# TweetyBoy.net
KiCad netlist of a schematic drawn in EAGLE
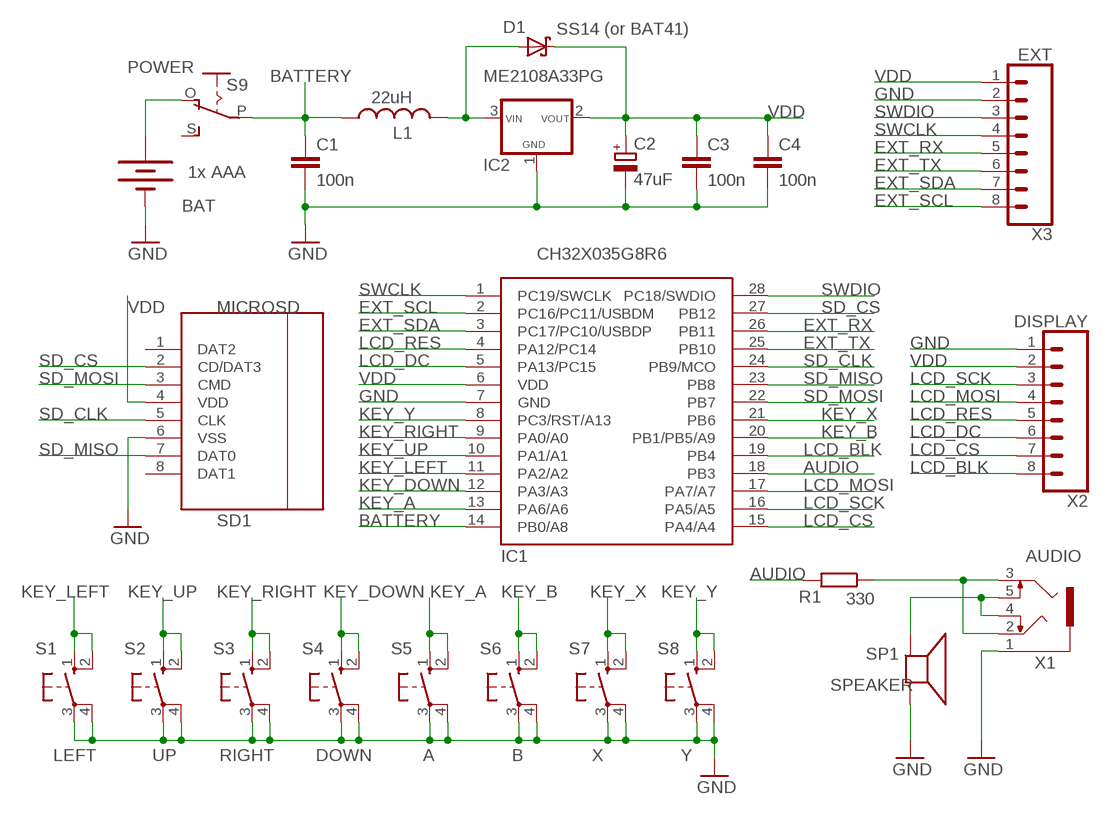
[diagram p0: schematic, sheet 1]

(export (version "E")
  (design (tool "Eeschema 10.0.6"))
  (components
    (comp (ref "BAT")
      (value "1x AAA")
      (footprint "eagle-import:BATTERY-AAA-KIT")
      (libsource (lib "eagle-import") (part "BATTERY-AAA_KIT"))
    )
    (comp (ref "C1")
      (value "100n")
      (footprint "eagle-import:C050-024X044")
      (libsource (lib "eagle-import") (part "C-EU050-024X044"))
    )
    (comp (ref "C2")
      (value "47uF")
      (footprint "eagle-import:E2-5")
      (libsource (lib "eagle-import") (part "CPOL-EUE2-5"))
    )
    (comp (ref "C3")
      (value "100n")
      (footprint "eagle-import:C050-024X044")
      (libsource (lib "eagle-import") (part "C-EU050-024X044"))
    )
    (comp (ref "C4")
      (value "100n")
      (footprint "eagle-import:C050-024X044")
      (libsource (lib "eagle-import") (part "C-EU050-024X044"))
    )
    (comp (ref "D1")
      (value "SS14 (or BAT41)")
      (footprint "eagle-import:DO35-7")
      (libsource (lib "eagle-import") (part "SCHOTTKY-DIODEDO35-7"))
    )
    (comp (ref "IC1")
      (value "CH32X035G8R6")
      (footprint "eagle-import:QSOP28")
      (libsource (lib "eagle-import") (part "CH32X035G8R6"))
    )
    (comp (ref "IC2")
      (value "ME2108A33PG")
      (footprint "eagle-import:SOT89-R")
      (libsource (lib "eagle-import") (part "ME2108A33PG"))
    )
    (comp (ref "L1")
      (value "22uH")
      (footprint "eagle-import:POWER-CHOKE_WE-TPC")
      (libsource (lib "eagle-import") (part "L-USWE-TPC"))
    )
    (comp (ref "R1")
      (value "330")
      (footprint "eagle-import:0204_7")
      (libsource (lib "eagle-import") (part "R-EU_0204/7"))
    )
    (comp (ref "S1")
      (value "LEFT")
      (footprint "eagle-import:B3F-10XX")
      (fields (field (name "MPN") "B3F-1000"))
      (libsource (lib "eagle-import") (part "10-XX"))
    )
    (comp (ref "S2")
      (value "UP")
      (footprint "eagle-import:B3F-10XX")
      (fields (field (name "MPN") "B3F-1000"))
      (libsource (lib "eagle-import") (part "10-XX"))
    )
    (comp (ref "S3")
      (value "RIGHT")
      (footprint "eagle-import:B3F-10XX")
      (fields (field (name "MPN") "B3F-1000"))
      (libsource (lib "eagle-import") (part "10-XX"))
    )
    (comp (ref "S4")
      (value "DOWN")
      (footprint "eagle-import:B3F-10XX")
      (fields (field (name "MPN") "B3F-1000"))
      (libsource (lib "eagle-import") (part "10-XX"))
    )
    (comp (ref "S5")
      (value "A")
      (footprint "eagle-import:B3F-10XX")
      (fields (field (name "MPN") "B3F-1000"))
      (libsource (lib "eagle-import") (part "10-XX"))
    )
    (comp (ref "S6")
      (value "B")
      (footprint "eagle-import:B3F-10XX")
      (fields (field (name "MPN") "B3F-1000"))
      (libsource (lib "eagle-import") (part "10-XX"))
    )
    (comp (ref "S7")
      (value "X")
      (footprint "eagle-import:B3F-10XX")
      (fields (field (name "MPN") "B3F-1000"))
      (libsource (lib "eagle-import") (part "10-XX"))
    )
    (comp (ref "S8")
      (value "Y")
      (footprint "eagle-import:B3F-10XX")
      (fields (field (name "MPN") "B3F-1000"))
      (libsource (lib "eagle-import") (part "10-XX"))
    )
    (comp (ref "S9")
      (value "POWER")
      (footprint "eagle-import:EG1218")
      (libsource (lib "eagle-import") (part "EG1218S"))
    )
    (comp (ref "SD1")
      (value "MICROSD")
      (footprint "eagle-import:MICROSD")
      (libsource (lib "eagle-import") (part "MICROSD"))
    )
    (comp (ref "SP1")
      (value "SPEAKER")
      (footprint "eagle-import:AL60P")
      (libsource (lib "eagle-import") (part "SPEAKER/AL60P"))
    )
    (comp (ref "X1")
      (value "AUDIO")
      (footprint "eagle-import:1503_09")
      (libsource (lib "eagle-import") (part "1503_09"))
    )
    (comp (ref "X2")
      (value "DISPLAY")
      (footprint "eagle-import:1X08_LONGPADS")
      (libsource (lib "eagle-import") (part "CONN_08LONGPADS"))
    )
    (comp (ref "X3")
      (value "EXT")
      (footprint "eagle-import:1X08_LONGPADS")
      (libsource (lib "eagle-import") (part "CONN_08LONGPADS"))
    )
  )
  (nets
    (net (code "1") (name "/AUDIO") (class "Default")
      (node (ref "IC1") (pin "18") (pinfunction "PB3_18") (pintype "bidirectional"))
      (node (ref "R1") (pin "2") (pinfunction "2_2") (pintype "passive"))
    )
    (net (code "2") (name "/BATTERY") (class "Default")
      (node (ref "C1") (pin "1") (pinfunction "1_1") (pintype "passive"))
      (node (ref "IC1") (pin "14") (pinfunction "PB0/A8_14") (pintype "bidirectional"))
      (node (ref "L1") (pin "1") (pinfunction "1_1") (pintype "passive"))
      (node (ref "S9") (pin "P") (pinfunction "P_P") (pintype "passive"))
    )
    (net (code "3") (name "/EXT_RX") (class "Default")
      (node (ref "IC1") (pin "26") (pinfunction "PB11_26") (pintype "bidirectional"))
      (node (ref "X3") (pin "5") (pinfunction "5_5") (pintype "passive"))
    )
    (net (code "4") (name "/EXT_SCL") (class "Default")
      (node (ref "IC1") (pin "2") (pinfunction "PC16/PC11/USBDM_2") (pintype "bidirectional"))
      (node (ref "X3") (pin "8") (pinfunction "8_8") (pintype "passive"))
    )
    (net (code "5") (name "/EXT_SDA") (class "Default")
      (node (ref "IC1") (pin "3") (pinfunction "PC17/PC10/USBDP_3") (pintype "bidirectional"))
      (node (ref "X3") (pin "7") (pinfunction "7_7") (pintype "passive"))
    )
    (net (code "6") (name "/EXT_TX") (class "Default")
      (node (ref "IC1") (pin "25") (pinfunction "PB10_25") (pintype "bidirectional"))
      (node (ref "X3") (pin "6") (pinfunction "6_6") (pintype "passive"))
    )
    (net (code "7") (name "/KEY_A") (class "Default")
      (node (ref "IC1") (pin "13") (pinfunction "PA6/A6_13") (pintype "bidirectional"))
      (node (ref "S5") (pin "1") (pinfunction "S_1") (pintype "passive"))
      (node (ref "S5") (pin "2") (pinfunction "S1_2") (pintype "passive"))
    )
    (net (code "8") (name "/KEY_B") (class "Default")
      (node (ref "IC1") (pin "20") (pinfunction "PB1/PB5/A9_20") (pintype "bidirectional"))
      (node (ref "S6") (pin "1") (pinfunction "S_1") (pintype "passive"))
      (node (ref "S6") (pin "2") (pinfunction "S1_2") (pintype "passive"))
    )
    (net (code "9") (name "/KEY_DOWN") (class "Default")
      (node (ref "IC1") (pin "12") (pinfunction "PA3/A3_12") (pintype "bidirectional"))
      (node (ref "S4") (pin "1") (pinfunction "S_1") (pintype "passive"))
      (node (ref "S4") (pin "2") (pinfunction "S1_2") (pintype "passive"))
    )
    (net (code "10") (name "/KEY_LEFT") (class "Default")
      (node (ref "IC1") (pin "11") (pinfunction "PA2/A2_11") (pintype "bidirectional"))
      (node (ref "S1") (pin "1") (pinfunction "S_1") (pintype "passive"))
      (node (ref "S1") (pin "2") (pinfunction "S1_2") (pintype "passive"))
    )
    (net (code "11") (name "/KEY_RIGHT") (class "Default")
      (node (ref "IC1") (pin "9") (pinfunction "PA0/A0_9") (pintype "bidirectional"))
      (node (ref "S3") (pin "1") (pinfunction "S_1") (pintype "passive"))
      (node (ref "S3") (pin "2") (pinfunction "S1_2") (pintype "passive"))
    )
    (net (code "12") (name "/KEY_UP") (class "Default")
      (node (ref "IC1") (pin "10") (pinfunction "PA1/A1_10") (pintype "bidirectional"))
      (node (ref "S2") (pin "1") (pinfunction "S_1") (pintype "passive"))
      (node (ref "S2") (pin "2") (pinfunction "S1_2") (pintype "passive"))
    )
    (net (code "13") (name "/KEY_X") (class "Default")
      (node (ref "IC1") (pin "21") (pinfunction "PB6_21") (pintype "bidirectional"))
      (node (ref "S7") (pin "1") (pinfunction "S_1") (pintype "passive"))
      (node (ref "S7") (pin "2") (pinfunction "S1_2") (pintype "passive"))
    )
    (net (code "14") (name "/KEY_Y") (class "Default")
      (node (ref "IC1") (pin "8") (pinfunction "PC3/RST/A13_8") (pintype "bidirectional"))
      (node (ref "S8") (pin "1") (pinfunction "S_1") (pintype "passive"))
      (node (ref "S8") (pin "2") (pinfunction "S1_2") (pintype "passive"))
    )
    (net (code "15") (name "/LCD_BLK") (class "Default")
      (node (ref "IC1") (pin "19") (pinfunction "PB4_19") (pintype "bidirectional"))
      (node (ref "X2") (pin "8") (pinfunction "8_8") (pintype "passive"))
    )
    (net (code "16") (name "/LCD_CS") (class "Default")
      (node (ref "IC1") (pin "15") (pinfunction "PA4/A4_15") (pintype "bidirectional"))
      (node (ref "X2") (pin "7") (pinfunction "7_7") (pintype "passive"))
    )
    (net (code "17") (name "/LCD_DC") (class "Default")
      (node (ref "IC1") (pin "5") (pinfunction "PA13/PC15_5") (pintype "bidirectional"))
      (node (ref "X2") (pin "6") (pinfunction "6_6") (pintype "passive"))
    )
    (net (code "18") (name "/LCD_MOSI") (class "Default")
      (node (ref "IC1") (pin "17") (pinfunction "PA7/A7_17") (pintype "bidirectional"))
      (node (ref "X2") (pin "4") (pinfunction "4_4") (pintype "passive"))
    )
    (net (code "19") (name "/LCD_RES") (class "Default")
      (node (ref "IC1") (pin "4") (pinfunction "PA12/PC14_4") (pintype "bidirectional"))
      (node (ref "X2") (pin "5") (pinfunction "5_5") (pintype "passive"))
    )
    (net (code "20") (name "/LCD_SCK") (class "Default")
      (node (ref "IC1") (pin "16") (pinfunction "PA5/A5_16") (pintype "bidirectional"))
      (node (ref "X2") (pin "3") (pinfunction "3_3") (pintype "passive"))
    )
    (net (code "21") (name "/SD_CLK") (class "Default")
      (node (ref "IC1") (pin "24") (pinfunction "PB9/MCO_24") (pintype "bidirectional"))
      (node (ref "SD1") (pin "5") (pinfunction "CLK_5") (pintype "bidirectional"))
    )
    (net (code "22") (name "/SD_CS") (class "Default")
      (node (ref "IC1") (pin "27") (pinfunction "PB12_27") (pintype "bidirectional"))
      (node (ref "SD1") (pin "2") (pinfunction "CD/DAT3_2") (pintype "bidirectional"))
    )
    (net (code "23") (name "/SD_MISO") (class "Default")
      (node (ref "IC1") (pin "23") (pinfunction "PB8_23") (pintype "bidirectional"))
      (node (ref "SD1") (pin "7") (pinfunction "DAT0_7") (pintype "bidirectional"))
    )
    (net (code "24") (name "/SD_MOSI") (class "Default")
      (node (ref "IC1") (pin "22") (pinfunction "PB7_22") (pintype "bidirectional"))
      (node (ref "SD1") (pin "3") (pinfunction "CMD_3") (pintype "bidirectional"))
    )
    (net (code "25") (name "/SWCLK") (class "Default")
      (node (ref "IC1") (pin "1") (pinfunction "PC19/SWCLK_1") (pintype "bidirectional"))
      (node (ref "X3") (pin "4") (pinfunction "4_4") (pintype "passive"))
    )
    (net (code "26") (name "/SWDIO") (class "Default")
      (node (ref "IC1") (pin "28") (pinfunction "PC18/SWDIO_28") (pintype "bidirectional"))
      (node (ref "X3") (pin "3") (pinfunction "3_3") (pintype "passive"))
    )
    (net (code "27") (name "/VDD") (class "Default")
      (node (ref "C2") (pin "+") (pinfunction "+_+") (pintype "passive"))
      (node (ref "C3") (pin "1") (pinfunction "1_1") (pintype "passive"))
      (node (ref "C4") (pin "1") (pinfunction "1_1") (pintype "passive"))
      (node (ref "D1") (pin "C") (pinfunction "C_C") (pintype "passive"))
      (node (ref "IC1") (pin "6") (pinfunction "VDD_6") (pintype "power_in"))
      (node (ref "IC2") (pin "2") (pinfunction "VOUT_2") (pintype "power_in"))
      (node (ref "SD1") (pin "4") (pinfunction "VDD_4") (pintype "bidirectional"))
      (node (ref "X2") (pin "2") (pinfunction "2_2") (pintype "passive"))
      (node (ref "X3") (pin "1") (pinfunction "1_1") (pintype "passive"))
    )
    (net (code "28") (name "GND") (class "Default")
      (node (ref "BAT") (pin "GND@1") (pinfunction "-_GND@1") (pintype "power_in"))
      (node (ref "C1") (pin "2") (pinfunction "2_2") (pintype "passive"))
      (node (ref "C2") (pin "-") (pinfunction "-_-") (pintype "passive"))
      (node (ref "C3") (pin "2") (pinfunction "2_2") (pintype "passive"))
      (node (ref "C4") (pin "2") (pinfunction "2_2") (pintype "passive"))
      (node (ref "IC1") (pin "7") (pinfunction "GND_7") (pintype "power_in"))
      (node (ref "IC2") (pin "1") (pinfunction "GND_1") (pintype "power_in"))
      (node (ref "S1") (pin "3") (pinfunction "P_3") (pintype "passive"))
      (node (ref "S1") (pin "4") (pinfunction "P1_4") (pintype "passive"))
      (node (ref "S2") (pin "3") (pinfunction "P_3") (pintype "passive"))
      (node (ref "S2") (pin "4") (pinfunction "P1_4") (pintype "passive"))
      (node (ref "S3") (pin "3") (pinfunction "P_3") (pintype "passive"))
      (node (ref "S3") (pin "4") (pinfunction "P1_4") (pintype "passive"))
      (node (ref "S4") (pin "3") (pinfunction "P_3") (pintype "passive"))
      (node (ref "S4") (pin "4") (pinfunction "P1_4") (pintype "passive"))
      (node (ref "S5") (pin "3") (pinfunction "P_3") (pintype "passive"))
      (node (ref "S5") (pin "4") (pinfunction "P1_4") (pintype "passive"))
      (node (ref "S6") (pin "3") (pinfunction "P_3") (pintype "passive"))
      (node (ref "S6") (pin "4") (pinfunction "P1_4") (pintype "passive"))
      (node (ref "S7") (pin "3") (pinfunction "P_3") (pintype "passive"))
      (node (ref "S7") (pin "4") (pinfunction "P1_4") (pintype "passive"))
      (node (ref "S8") (pin "3") (pinfunction "P_3") (pintype "passive"))
      (node (ref "S8") (pin "4") (pinfunction "P1_4") (pintype "passive"))
      (node (ref "SD1") (pin "6") (pinfunction "VSS_6") (pintype "bidirectional"))
      (node (ref "SP1") (pin "2") (pinfunction "-_2") (pintype "passive"))
      (node (ref "X1") (pin "1") (pinfunction "1_1") (pintype "passive"))
      (node (ref "X2") (pin "1") (pinfunction "1_1") (pintype "passive"))
      (node (ref "X3") (pin "2") (pinfunction "2_2") (pintype "passive"))
    )
    (net (code "29") (name "Net-(BAT-+)") (class "Default")
      (node (ref "BAT") (pin "PWR@1") (pinfunction "+_PWR@1") (pintype "power_in"))
      (node (ref "S9") (pin "O") (pinfunction "O_O") (pintype "passive"))
    )
    (net (code "30") (name "Net-(IC2-IN)") (class "Default")
      (node (ref "D1") (pin "A") (pinfunction "A_A") (pintype "passive"))
      (node (ref "IC2") (pin "3") (pinfunction "IN_3") (pintype "power_in"))
      (node (ref "L1") (pin "2") (pinfunction "2_2") (pintype "passive"))
    )
    (net (code "31") (name "Net-(R1-Pad1)") (class "Default")
      (node (ref "R1") (pin "1") (pinfunction "1_1") (pintype "passive"))
      (node (ref "X1") (pin "2") (pinfunction "2_2") (pintype "passive"))
      (node (ref "X1") (pin "3") (pinfunction "3_3") (pintype "passive"))
    )
    (net (code "32") (name "Net-(SP1-+)") (class "Default")
      (node (ref "SP1") (pin "1") (pinfunction "+_1") (pintype "passive"))
      (node (ref "X1") (pin "4") (pinfunction "4_4") (pintype "passive"))
      (node (ref "X1") (pin "5") (pinfunction "5_5") (pintype "passive"))
    )
    (net (code "33") (name "unconnected-(S9-PadS)") (class "Default")
      (node (ref "S9") (pin "S") (pinfunction "S_S") (pintype "passive"))
    )
    (net (code "34") (name "unconnected-(SD1-DAT1-Pad8)") (class "Default")
      (node (ref "SD1") (pin "8") (pinfunction "DAT1_8") (pintype "bidirectional"))
    )
    (net (code "35") (name "unconnected-(SD1-DAT2-Pad1)") (class "Default")
      (node (ref "SD1") (pin "1") (pinfunction "DAT2_1") (pintype "bidirectional"))
    )
  )
)
